# MCP2515_Module.net
KiCad netlist of a schematic drawn in Altium Designer
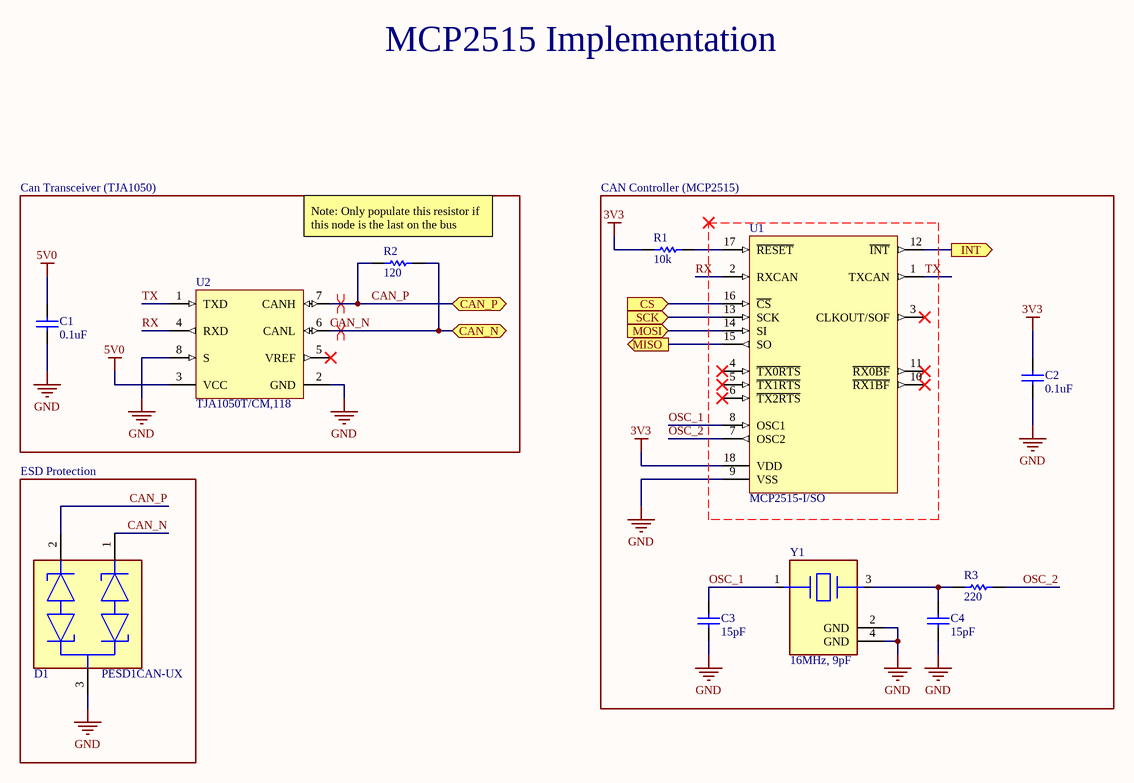
[diagram p0: MCP2515 Module.SchDoc]

(export (version "E")
  (design (tool "Eeschema 10.0.6"))
  (components
    (comp (ref "C1")
      (value "0.1uF")
      (footprint "CAPC2013X88X50NL20T25")
      (fields
        (field (name "PART NUMBER") "C0805C104K5RACTU")
        (field (name "MANUFACTURER") "Kemet")
        (field (name "TOLERANCE") "10%")
      )
      (libsource (lib "Altium Content Vault") (part "CAP"))
    )
    (comp (ref "C2")
      (value "0.1uF")
      (footprint "CAPC2013X88X50NL20T25")
      (fields
        (field (name "PART NUMBER") "C0805C104K5RACTU")
        (field (name "MANUFACTURER") "Kemet")
        (field (name "TOLERANCE") "10%")
      )
      (libsource (lib "Altium Content Vault") (part "CAP"))
    )
    (comp (ref "C3")
      (value "15pF")
      (footprint "CAPC2013X140X50LL20T25")
      (fields
        (field (name "PART NUMBER") "08055A150JAT2A")
        (field (name "MANUFACTURER") "AVX Interconnect / Elco")
        (field (name "TOLERANCE") "5%")
      )
      (libsource (lib "Altium Content Vault") (part "CAP"))
    )
    (comp (ref "C4")
      (value "15pF")
      (footprint "CAPC2013X140X50LL20T25")
      (fields
        (field (name "PART NUMBER") "08055A150JAT2A")
        (field (name "MANUFACTURER") "AVX Interconnect / Elco")
        (field (name "TOLERANCE") "5%")
      )
      (libsource (lib "Altium Content Vault") (part "CAP"))
    )
    (comp (ref "D1")
      (value "PESD1CAN-UX")
      (footprint "FP-SOT323-MFG")
      (description "TVS DIODE 24V 50V SC70-3")
      (fields (field (name "MANUFACTURER") "Nexperia"))
      (libsource (lib "Altium Content Vault") (part "04d57993b6b7b0f5b3c95ba4f97dea0"))
    )
    (comp (ref "R1")
      (value "10k")
      (footprint "RESC2013X60X40LL20T25_A")
      (fields
        (field (name "TOLERANCE") "0.1%")
        (field (name "MANUFACTURER") "Panasonic")
        (field (name "MANUFACTURER PART NUMBER") "ERA-6AEB103V")
      )
      (libsource (lib "Altium Content Vault") (part "RES-2"))
    )
    (comp (ref "R2")
      (value "120")
      (footprint "RESC2013X70X40NL20T20")
      (description "Chip Resistor, 120 Ohm, +/- 1%, 0.125 W, -55 to 155 degC, 0805 (2012 Metric), RoHS, Tape and Reel")
      (fields
        (field (name "MANUFACTURER") "Panasonic")
        (field (name "MANUFACTURER PART NUMBER") "ERJ-6ENF1200V")
      )
      (libsource (lib "Altium Content Vault") (part "RES-2"))
    )
    (comp (ref "R3")
      (value "220")
      (footprint "RESC2013X70X40NL20T20")
      (fields
        (field (name "PART NUMBER") "ERJ6ENF2200V")
        (field (name "MANUFACTURER") "Panasonic")
        (field (name "MANUFACTURER PART NUMBER") "ERJ-6ENF2200V")
      )
      (libsource (lib "Altium Content Vault") (part "RES"))
    )
    (comp (ref "U1")
      (value "MCP2515-I/SO")
      (footprint "SOIC-SO18_L")
      (description "Stand-Alone CAN Controller With SPI Interface, 18-Pin SOIC, Industrial Temperature")
      (fields (field (name "MANUFACTURER") "Microchip"))
      (libsource (lib "Altium Content Vault") (part "COM-CAN-MCP2515-18"))
    )
    (comp (ref "U2")
      (value "TJA1050T/CM,118")
      (footprint "NXP-SOT96-1_M")
      (fields (field (name "MANUFACTURER") "NXP Semiconductors"))
      (libsource (lib "Altium Content Vault") (part "NXP-TJA1050-8"))
    )
    (comp (ref "Y1")
      (value "16MHz, 9pF")
      (footprint "FP-TSX-3225-MFG")
      (description "CRYSTAL 16.00 MHZ 9PF SMD")
      (fields
        (field (name "MANUFACTURER PART NUMBER") "TSX-3225 16.0000MF18X-AC0")
        (field (name "OCTOPART") "https://octopart.com/tsx-3225+16.0000mf18x-ac0-epson-58756552")
      )
      (libsource (lib "Altium Content Vault") (part "a9e65936d6f6a8cd8abf4b50f2664b9"))
    )
  )
  (nets
    (net (code "1") (name "/CAN_N") (class "Default")
      (node (ref "D1") (pin "1") (pinfunction "cathode_1_1") (pintype "passive"))
      (node (ref "R2") (pin "2") (pinfunction "2_2") (pintype "passive"))
      (node (ref "U2") (pin "6") (pinfunction "CANL_6") (pintype "bidirectional"))
    )
    (net (code "2") (name "/CAN_P") (class "Default")
      (node (ref "D1") (pin "2") (pinfunction "cathode_2_2") (pintype "passive"))
      (node (ref "R2") (pin "1") (pinfunction "1_1") (pintype "passive"))
      (node (ref "U2") (pin "7") (pinfunction "CANH_7") (pintype "bidirectional"))
    )
    (net (code "3") (name "/CS") (class "Default")
      (node (ref "U1") (pin "16") (pinfunction "~{CS}_16") (pintype "input"))
    )
    (net (code "4") (name "/INT") (class "Default")
      (node (ref "U1") (pin "12") (pinfunction "~{INT}_12") (pintype "output"))
    )
    (net (code "5") (name "/MISO") (class "Default")
      (node (ref "U1") (pin "15") (pinfunction "SO_15") (pintype "output"))
    )
    (net (code "6") (name "/MOSI") (class "Default")
      (node (ref "U1") (pin "14") (pinfunction "SI_14") (pintype "input"))
    )
    (net (code "7") (name "/OSC_1") (class "Default")
      (node (ref "C3") (pin "1") (pinfunction "1_1") (pintype "passive"))
      (node (ref "U1") (pin "8") (pinfunction "OSC1_8") (pintype "input"))
      (node (ref "Y1") (pin "1") (pinfunction "1_1") (pintype "passive"))
    )
    (net (code "8") (name "/OSC_2") (class "Default")
      (node (ref "R3") (pin "1") (pinfunction "1_1") (pintype "passive"))
      (node (ref "U1") (pin "7") (pinfunction "OSC2_7") (pintype "output"))
    )
    (net (code "9") (name "/RX") (class "Default")
      (node (ref "U1") (pin "2") (pinfunction "RXCAN_2") (pintype "input"))
      (node (ref "U2") (pin "4") (pinfunction "RXD_4") (pintype "output"))
    )
    (net (code "10") (name "/SCK") (class "Default")
      (node (ref "U1") (pin "13") (pinfunction "SCK_13") (pintype "input"))
    )
    (net (code "11") (name "/TX") (class "Default")
      (node (ref "U1") (pin "1") (pinfunction "TXCAN_1") (pintype "output"))
      (node (ref "U2") (pin "1") (pinfunction "TXD_1") (pintype "input"))
    )
    (net (code "12") (name "3V3") (class "Default")
      (node (ref "C2") (pin "2") (pinfunction "2_2") (pintype "passive"))
      (node (ref "R1") (pin "1") (pinfunction "1_1") (pintype "passive"))
      (node (ref "U1") (pin "18") (pinfunction "VDD_18") (pintype "power_in"))
    )
    (net (code "13") (name "5V0") (class "Default")
      (node (ref "C1") (pin "2") (pinfunction "2_2") (pintype "passive"))
      (node (ref "U2") (pin "3") (pinfunction "VCC_3") (pintype "power_in"))
    )
    (net (code "14") (name "GND") (class "Default")
      (node (ref "C1") (pin "1") (pinfunction "1_1") (pintype "passive"))
      (node (ref "C2") (pin "1") (pinfunction "1_1") (pintype "passive"))
      (node (ref "C3") (pin "2") (pinfunction "2_2") (pintype "passive"))
      (node (ref "C4") (pin "2") (pinfunction "2_2") (pintype "passive"))
      (node (ref "D1") (pin "3") (pinfunction "common_cathode_3") (pintype "passive"))
      (node (ref "U1") (pin "9") (pinfunction "VSS_9") (pintype "power_in"))
      (node (ref "U2") (pin "2") (pinfunction "GND_2") (pintype "power_in"))
      (node (ref "U2") (pin "8") (pinfunction "S_8") (pintype "input"))
      (node (ref "Y1") (pin "2") (pinfunction "GND_2") (pintype "power_in"))
      (node (ref "Y1") (pin "4") (pinfunction "GND_4") (pintype "power_in"))
    )
    (net (code "15") (name "Net-(C4-Pad1)") (class "Default")
      (node (ref "C4") (pin "1") (pinfunction "1_1") (pintype "passive"))
      (node (ref "R3") (pin "2") (pinfunction "2_2") (pintype "passive"))
      (node (ref "Y1") (pin "3") (pinfunction "3_3") (pintype "passive"))
    )
    (net (code "16") (name "Net-(U1-~{RESET})") (class "Default")
      (node (ref "R1") (pin "2") (pinfunction "2_2") (pintype "passive"))
      (node (ref "U1") (pin "17") (pinfunction "~{RESET}_17") (pintype "input"))
    )
    (net (code "17") (name "unconnected-(U1-CLKOUT{slash}SOF-Pad3)") (class "Default")
      (node (ref "U1") (pin "3") (pinfunction "CLKOUT/SOF_3") (pintype "output+no_connect"))
    )
    (net (code "18") (name "unconnected-(U1-~{RX0BF}-Pad11)") (class "Default")
      (node (ref "U1") (pin "11") (pinfunction "~{RX0BF}_11") (pintype "output+no_connect"))
    )
    (net (code "19") (name "unconnected-(U1-~{RX1BF}-Pad10)") (class "Default")
      (node (ref "U1") (pin "10") (pinfunction "~{RX1BF}_10") (pintype "output+no_connect"))
    )
    (net (code "20") (name "unconnected-(U1-~{TX0RTS}-Pad4)") (class "Default")
      (node (ref "U1") (pin "4") (pinfunction "~{TX0RTS}_4") (pintype "input+no_connect"))
    )
    (net (code "21") (name "unconnected-(U1-~{TX1RTS}-Pad5)") (class "Default")
      (node (ref "U1") (pin "5") (pinfunction "~{TX1RTS}_5") (pintype "input+no_connect"))
    )
    (net (code "22") (name "unconnected-(U1-~{TX2RTS}-Pad6)") (class "Default")
      (node (ref "U1") (pin "6") (pinfunction "~{TX2RTS}_6") (pintype "input+no_connect"))
    )
    (net (code "23") (name "unconnected-(U2-VREF-Pad5)") (class "Default")
      (node (ref "U2") (pin "5") (pinfunction "VREF_5") (pintype "output+no_connect"))
    )
  )
)
